# bmsMaster_power.net
KiCad netlist of a schematic drawn in Altium Designer
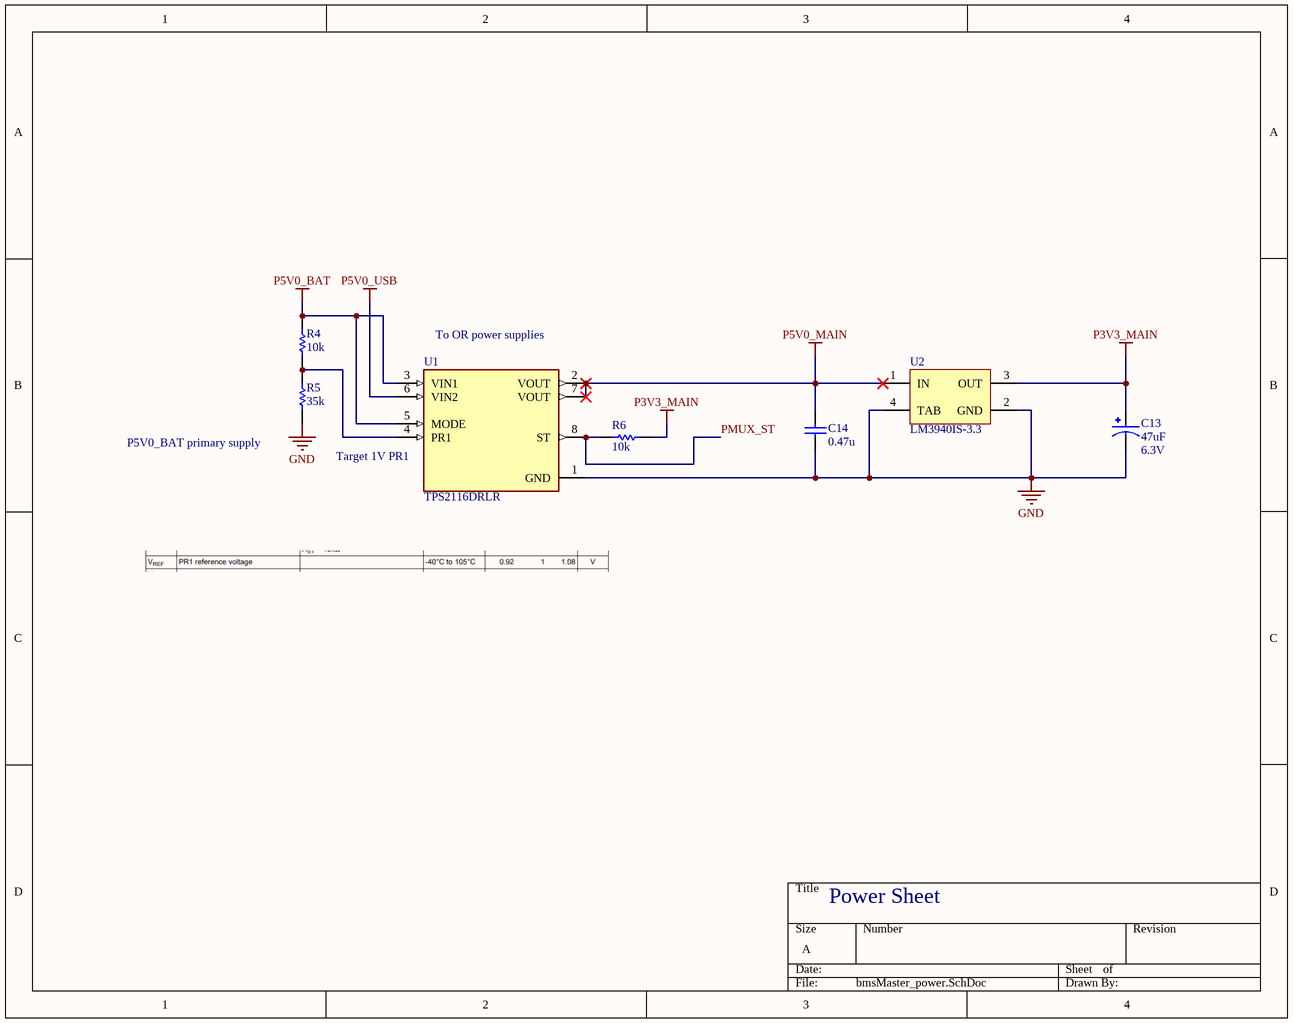
[diagram p0: bmsMaster_power.SchDoc]

(export (version "E")
  (design (tool "Eeschema 10.0.6"))
  (components
    (comp (ref "C13")
      (value "47uF")
      (footprint "EEE-HA0J470WR:CAP_EEEHA0J470WR")
      (fields
        (field (name "MP") "EEEHA0J470WR")
        (field (name "MF") "{'manufacturer': u'Panasonic'}")
        (field (name "RATING") "6.3V")
      )
      (libsource (lib "*") (part "EEEHA0J470WR"))
    )
    (comp (ref "C14")
      (value "0.47u")
      (description "Capacitor")
      (libsource (lib "Simulation Generic Components") (part "Capacitor"))
    )
    (comp (ref "R4")
      (value "10k")
      (description "Resistor")
      (libsource (lib "Simulation Generic Components") (part "Resistor"))
    )
    (comp (ref "R5")
      (value "35k")
      (description "Resistor")
      (libsource (lib "Simulation Generic Components") (part "Resistor"))
    )
    (comp (ref "R6")
      (value "10k")
      (description "Resistor")
      (libsource (lib "Simulation Generic Components") (part "Resistor"))
    )
    (comp (ref "U1")
      (value "TPS2116DRLR")
      (footprint "TPS2116DRLR:SOTFL50P160X60-8N")
      (description "1.6 V to 5.5 V, 2.5-A Low IQ Power Mux with Manual and Priority Switchover")
      (fields (field (name "MF") "{'manufacturer': u'Texas Instruments'}"))
      (libsource (lib "*") (part "TPS2116DRLR"))
    )
    (comp (ref "U2")
      (value "LM3940IS-3.3")
      (footprint "KTT0003B_N")
      (description "1A Low Dropout Regulator for 5V to 3.3V Conversion, 3-pin TO-263")
      (fields (field (name "MANUFACTURER") "Texas Instruments"))
      (libsource (lib "Altium Content Vault") (part "PM-REG-LM2940-TO4"))
    )
  )
  (nets
    (net (code "1") (name "/PMUX_ST") (class "Default")
      (node (ref "R6") (pin "2") (pinfunction "2_2") (pintype "passive"))
      (node (ref "U1") (pin "8") (pinfunction "ST_8") (pintype "output"))
    )
    (net (code "2") (name "GND") (class "Default")
      (node (ref "C13") (pin "2") (pinfunction "2_2") (pintype "passive"))
      (node (ref "C14") (pin "1") (pinfunction "1_1") (pintype "passive"))
      (node (ref "R5") (pin "1") (pinfunction "1_1") (pintype "passive"))
      (node (ref "U1") (pin "1") (pinfunction "GND_1") (pintype "power_in"))
      (node (ref "U2") (pin "2") (pinfunction "GND_2") (pintype "power_in"))
      (node (ref "U2") (pin "4") (pinfunction "TAB_4") (pintype "power_in"))
    )
    (net (code "3") (name "Net-(U1-PR1)") (class "Default")
      (node (ref "R4") (pin "1") (pinfunction "1_1") (pintype "passive"))
      (node (ref "R5") (pin "2") (pinfunction "2_2") (pintype "passive"))
      (node (ref "U1") (pin "4") (pinfunction "PR1_4") (pintype "input"))
    )
    (net (code "4") (name "P3V3_MAIN") (class "Default")
      (node (ref "C13") (pin "1") (pinfunction "1_1") (pintype "passive"))
      (node (ref "R6") (pin "1") (pinfunction "1_1") (pintype "passive"))
      (node (ref "U2") (pin "3") (pinfunction "OUT_3") (pintype "power_in"))
    )
    (net (code "5") (name "P5V0_BAT") (class "Default")
      (node (ref "R4") (pin "2") (pinfunction "2_2") (pintype "passive"))
      (node (ref "U1") (pin "3") (pinfunction "VIN1_3") (pintype "input"))
      (node (ref "U1") (pin "5") (pinfunction "MODE_5") (pintype "input"))
    )
    (net (code "6") (name "P5V0_MAIN") (class "Default")
      (node (ref "C14") (pin "2") (pinfunction "2_2") (pintype "passive"))
      (node (ref "U1") (pin "2") (pinfunction "VOUT_2") (pintype "output"))
      (node (ref "U1") (pin "7") (pinfunction "VOUT_7") (pintype "output"))
      (node (ref "U2") (pin "1") (pinfunction "IN_1") (pintype "power_in"))
    )
    (net (code "7") (name "P5V0_USB") (class "Default")
      (node (ref "U1") (pin "6") (pinfunction "VIN2_6") (pintype "input"))
    )
  )
)
